# ETHERNET.net
KiCad netlist of a schematic drawn in Altium Designer
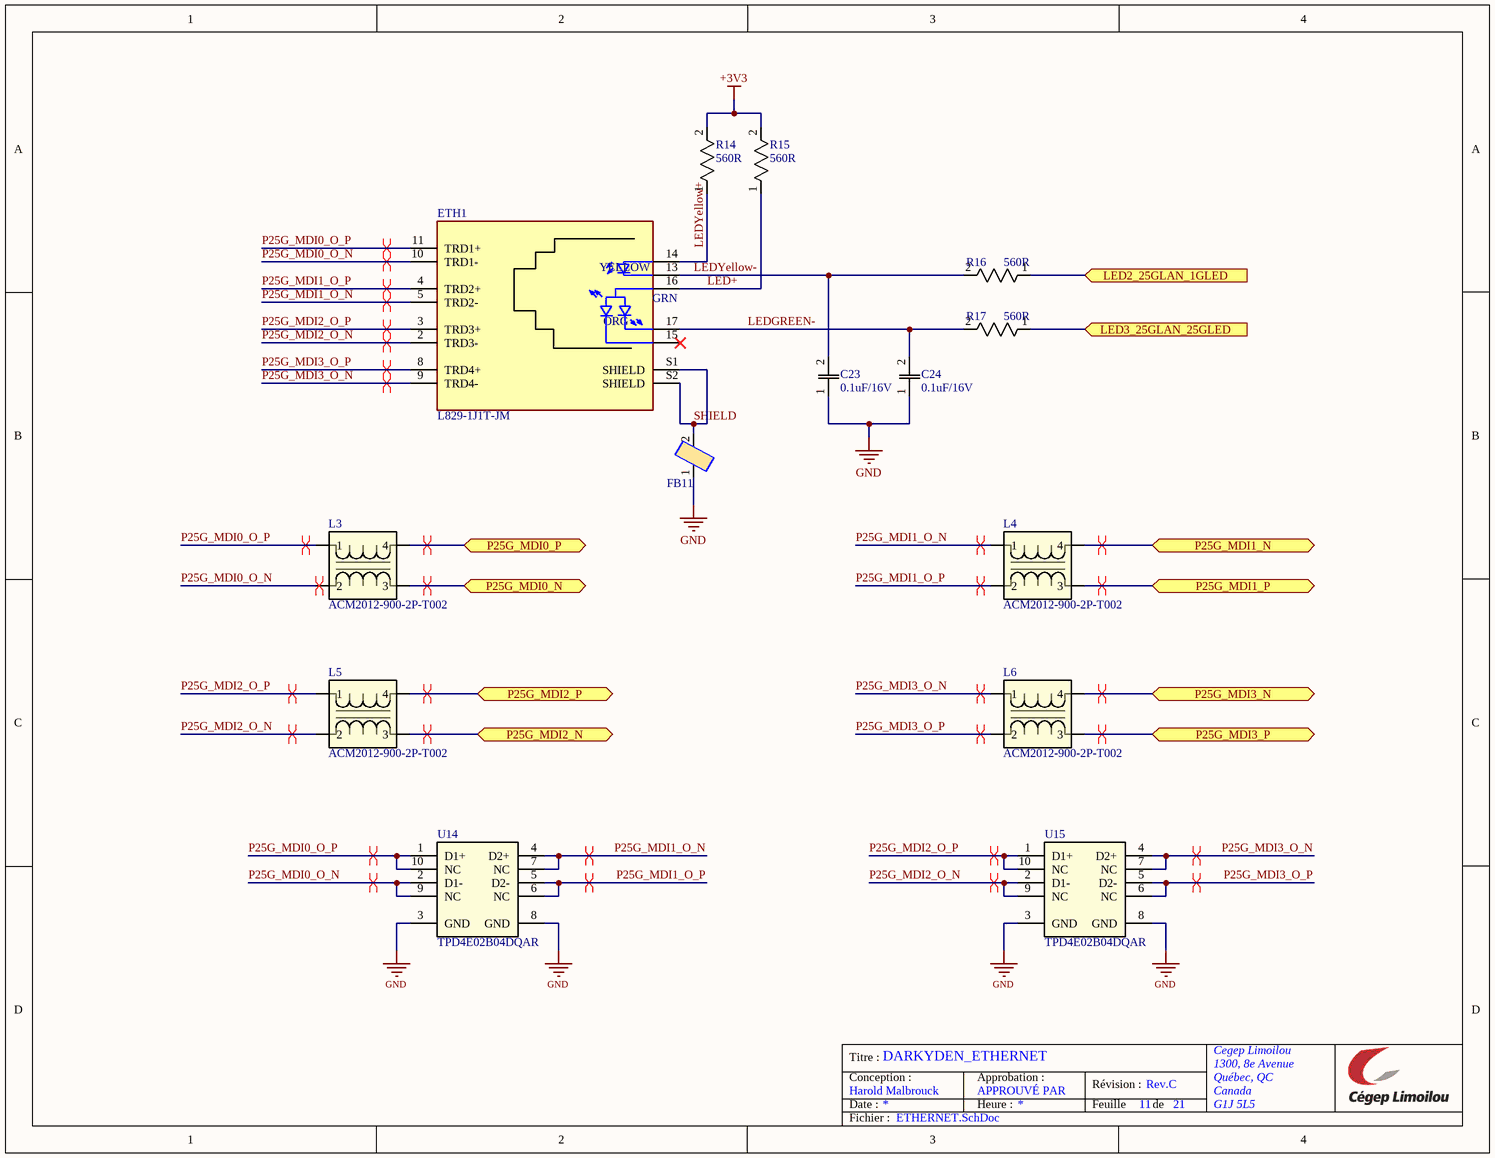
[diagram p0: ETHERNET.SchDoc]

(export (version "E")
  (design (tool "Eeschema 10.0.6"))
  (components
    (comp (ref "C23")
      (value "0.1uF/16V")
      (footprint "C0805")
      (description "0.1uF/16V ±10% X7R 0805 (2012METRIC) Ceramic Capacitor SMD Auto X7R")
      (fields
        (field (name "MANUFACTURER") "KEMET")
        (field (name "MANUFACTURER PART NUMBER") "C0805C104K5RACTU")
      )
      (libsource (lib "DARKYDEN") (part "C0805C104K4RACAUTO"))
    )
    (comp (ref "C24")
      (value "0.1uF/16V")
      (footprint "C0805")
      (description "0.1uF/16V ±10% X7R 0805 (2012METRIC) Ceramic Capacitor SMD Auto X7R")
      (fields
        (field (name "MANUFACTURER") "KEMET")
        (field (name "MANUFACTURER PART NUMBER") "C0805C104K5RACTU")
      )
      (libsource (lib "DARKYDEN") (part "C0805C104K4RACAUTO"))
    )
    (comp (ref "ETH1")
      (value "L829-1J1T-JM")
      (footprint "RJ-45")
      (description "Modular Connectors / Ethernet Connectors 1x1 2.5GBT MagJack")
      (fields
        (field (name "DIGI-KEY_PART_NUMBER") "507-2068-ND")
        (field (name "MF") "Bel Magnetic Solutions")
      )
      (libsource (lib "L829-1J1T-JM") (part "L829-1J1T-JM"))
    )
    (comp (ref "FB11")
      (value "220R / 100MHz")
      (footprint "SamacSys:BLM18SP221SN1B")
      (description "Ferrite Beads Multi-Layer 220Ohm 25% 100MHz 2A 50mOhm DCR 0603 Paper T/R")
      (fields
        (field (name "MOUSER PART NUMBER") "81-BLM18EG221SN1D")
        (field (name "ARROW PART NUMBER") "BLM18EG221SN1D")
      )
      (libsource (lib "SamacSys") (part "BLM18EG221SN1D"))
    )
    (comp (ref "L3")
      (value "ACM2012-900-2P-T002")
      (footprint "SamacSys:ACM20129002PT002")
      (description "Ferrite Beads Wirewound Common Mode Filter 90Ohm 100MHz 400mA 0805 T/R")
      (fields (field (name "MOUSER PART NUMBER") "810-ACM20129002PT002") (field (name "MANUFACTURER") "TDK"))
      (libsource (lib "SamacSys") (part "ACM2012-900-2P-T002"))
    )
    (comp (ref "L4")
      (value "ACM2012-900-2P-T002")
      (footprint "SamacSys:ACM20129002PT002")
      (description "Ferrite Beads Wirewound Common Mode Filter 90Ohm 100MHz 400mA 0805 T/R")
      (fields (field (name "MOUSER PART NUMBER") "810-ACM20129002PT002") (field (name "MANUFACTURER") "TDK"))
      (libsource (lib "SamacSys") (part "ACM2012-900-2P-T002"))
    )
    (comp (ref "L5")
      (value "ACM2012-900-2P-T002")
      (footprint "SamacSys:ACM20129002PT002")
      (description "Ferrite Beads Wirewound Common Mode Filter 90Ohm 100MHz 400mA 0805 T/R")
      (fields (field (name "MOUSER PART NUMBER") "810-ACM20129002PT002") (field (name "MANUFACTURER") "TDK"))
      (libsource (lib "SamacSys") (part "ACM2012-900-2P-T002"))
    )
    (comp (ref "L6")
      (value "ACM2012-900-2P-T002")
      (footprint "SamacSys:ACM20129002PT002")
      (description "Ferrite Beads Wirewound Common Mode Filter 90Ohm 100MHz 400mA 0805 T/R")
      (fields (field (name "MOUSER PART NUMBER") "810-ACM20129002PT002") (field (name "MANUFACTURER") "TDK"))
      (libsource (lib "SamacSys") (part "ACM2012-900-2P-T002"))
    )
    (comp (ref "R14")
      (value "560R")
      (footprint "RESC1608X55N")
      (description "560 Ohm, ï¿½ 1%, 100 mW, 0603 [1608 Metric], Thick Film, Precision")
      (fields
        (field (name "MANUFACTURER") "Panasonic")
        (field (name "MANUFACTURER PART NUMBER") "ERJ-3EKF5600V")
      )
      (libsource (lib "DARKYDEN") (part "ERJ-3EKF5600V"))
    )
    (comp (ref "R15")
      (value "560R")
      (footprint "RESC1608X55N")
      (description "560 Ohm, ï¿½ 1%, 100 mW, 0603 [1608 Metric], Thick Film, Precision")
      (fields
        (field (name "MANUFACTURER") "Panasonic")
        (field (name "MANUFACTURER PART NUMBER") "ERJ-3EKF5600V")
      )
      (libsource (lib "DARKYDEN") (part "ERJ-3EKF5600V"))
    )
    (comp (ref "R16")
      (value "560R")
      (footprint "RESC1608X55N")
      (description "560 Ohm, ï¿½ 1%, 100 mW, 0603 [1608 Metric], Thick Film, Precision")
      (fields
        (field (name "MANUFACTURER") "Panasonic")
        (field (name "MANUFACTURER PART NUMBER") "ERJ-3EKF5600V")
      )
      (libsource (lib "DARKYDEN") (part "ERJ-3EKF5600V"))
    )
    (comp (ref "R17")
      (value "560R")
      (footprint "RESC1608X55N")
      (description "560 Ohm, ï¿½ 1%, 100 mW, 0603 [1608 Metric], Thick Film, Precision")
      (fields
        (field (name "MANUFACTURER") "Panasonic")
        (field (name "MANUFACTURER PART NUMBER") "ERJ-3EKF5600V")
      )
      (libsource (lib "DARKYDEN") (part "ERJ-3EKF5600V"))
    )
    (comp (ref "U14")
      (value "TPD4E02B04DQAR")
      (footprint "DQA0010A")
      (description "TVS DIODE 3.6V 8.8V 10USON / 4-Channel ESD Protection Diode for USB Type-C and HDMI 2.0")
      (fields (field (name "MANUFACTURER") "Texas Instruments"))
      (libsource (lib "TPD4E02B04DQAR") (part "TPD4E02B04DQAR"))
    )
    (comp (ref "U15")
      (value "TPD4E02B04DQAR")
      (footprint "DQA0010A")
      (description "TVS DIODE 3.6V 8.8V 10USON / 4-Channel ESD Protection Diode for USB Type-C and HDMI 2.0")
      (fields (field (name "MANUFACTURER") "Texas Instruments"))
      (libsource (lib "TPD4E02B04DQAR") (part "TPD4E02B04DQAR"))
    )
  )
  (nets
    (net (code "1") (name "+3V3") (class "Default")
      (node (ref "R14") (pin "2") (pinfunction "2_2") (pintype "passive"))
      (node (ref "R15") (pin "2") (pinfunction "2_2") (pintype "passive"))
    )
    (net (code "2") (name "/LED+") (class "Default")
      (node (ref "ETH1") (pin "16") (pinfunction "CA_16") (pintype "passive"))
      (node (ref "R15") (pin "1") (pinfunction "1_1") (pintype "passive"))
    )
    (net (code "3") (name "/LED2_25GLAN_1GLED") (class "Default")
      (node (ref "R16") (pin "1") (pinfunction "1_1") (pintype "passive"))
    )
    (net (code "4") (name "/LED3_25GLAN_25GLED") (class "Default")
      (node (ref "R17") (pin "1") (pinfunction "1_1") (pintype "passive"))
    )
    (net (code "5") (name "/LEDGREEN-") (class "Default")
      (node (ref "C24") (pin "2") (pinfunction "2_2") (pintype "passive"))
      (node (ref "ETH1") (pin "17") (pinfunction "GK_1_17") (pintype "passive"))
      (node (ref "R17") (pin "2") (pinfunction "2_2") (pintype "passive"))
    )
    (net (code "6") (name "/LEDYellow+") (class "Default")
      (node (ref "ETH1") (pin "14") (pinfunction "YA_1_14") (pintype "passive"))
      (node (ref "R14") (pin "1") (pinfunction "1_1") (pintype "passive"))
    )
    (net (code "7") (name "/LEDYellow-") (class "Default")
      (node (ref "C23") (pin "2") (pinfunction "2_2") (pintype "passive"))
      (node (ref "ETH1") (pin "13") (pinfunction "YK_1_13") (pintype "passive"))
      (node (ref "R16") (pin "2") (pinfunction "2_2") (pintype "passive"))
    )
    (net (code "8") (name "/P25G_MDI0_N") (class "Default")
      (node (ref "L3") (pin "3") (pinfunction "3_3") (pintype "passive"))
    )
    (net (code "9") (name "/P25G_MDI0_O_N") (class "Default")
      (node (ref "ETH1") (pin "10") (pinfunction "TRD1-_10") (pintype "passive"))
      (node (ref "L3") (pin "2") (pinfunction "2_2") (pintype "passive"))
      (node (ref "U14") (pin "2") (pinfunction "D1-_2") (pintype "passive"))
      (node (ref "U14") (pin "9") (pinfunction "NC_9") (pintype "passive"))
    )
    (net (code "10") (name "/P25G_MDI0_O_P") (class "Default")
      (node (ref "ETH1") (pin "11") (pinfunction "TRD1+_11") (pintype "passive"))
      (node (ref "L3") (pin "1") (pinfunction "1_1") (pintype "passive"))
      (node (ref "U14") (pin "1") (pinfunction "D1+_1") (pintype "passive"))
      (node (ref "U14") (pin "10") (pinfunction "NC_10") (pintype "passive"))
    )
    (net (code "11") (name "/P25G_MDI0_P") (class "Default")
      (node (ref "L3") (pin "4") (pinfunction "4_4") (pintype "passive"))
    )
    (net (code "12") (name "/P25G_MDI1_N") (class "Default")
      (node (ref "L4") (pin "4") (pinfunction "4_4") (pintype "passive"))
    )
    (net (code "13") (name "/P25G_MDI1_O_N") (class "Default")
      (node (ref "ETH1") (pin "5") (pinfunction "TRD2-_5") (pintype "passive"))
      (node (ref "L4") (pin "1") (pinfunction "1_1") (pintype "passive"))
      (node (ref "U14") (pin "4") (pinfunction "D2+_4") (pintype "passive"))
      (node (ref "U14") (pin "7") (pinfunction "NC_7") (pintype "passive"))
    )
    (net (code "14") (name "/P25G_MDI1_O_P") (class "Default")
      (node (ref "ETH1") (pin "4") (pinfunction "TRD2+_4") (pintype "passive"))
      (node (ref "L4") (pin "2") (pinfunction "2_2") (pintype "passive"))
      (node (ref "U14") (pin "5") (pinfunction "D2-_5") (pintype "passive"))
      (node (ref "U14") (pin "6") (pinfunction "NC_6") (pintype "passive"))
    )
    (net (code "15") (name "/P25G_MDI1_P") (class "Default")
      (node (ref "L4") (pin "3") (pinfunction "3_3") (pintype "passive"))
    )
    (net (code "16") (name "/P25G_MDI2_N") (class "Default")
      (node (ref "L5") (pin "3") (pinfunction "3_3") (pintype "passive"))
    )
    (net (code "17") (name "/P25G_MDI2_O_N") (class "Default")
      (node (ref "ETH1") (pin "2") (pinfunction "TRD3-_2") (pintype "passive"))
      (node (ref "L5") (pin "2") (pinfunction "2_2") (pintype "passive"))
      (node (ref "U15") (pin "2") (pinfunction "D1-_2") (pintype "passive"))
      (node (ref "U15") (pin "9") (pinfunction "NC_9") (pintype "passive"))
    )
    (net (code "18") (name "/P25G_MDI2_O_P") (class "Default")
      (node (ref "ETH1") (pin "3") (pinfunction "TRD3+_3") (pintype "passive"))
      (node (ref "L5") (pin "1") (pinfunction "1_1") (pintype "passive"))
      (node (ref "U15") (pin "1") (pinfunction "D1+_1") (pintype "passive"))
      (node (ref "U15") (pin "10") (pinfunction "NC_10") (pintype "passive"))
    )
    (net (code "19") (name "/P25G_MDI2_P") (class "Default")
      (node (ref "L5") (pin "4") (pinfunction "4_4") (pintype "passive"))
    )
    (net (code "20") (name "/P25G_MDI3_N") (class "Default")
      (node (ref "L6") (pin "4") (pinfunction "4_4") (pintype "passive"))
    )
    (net (code "21") (name "/P25G_MDI3_O_N") (class "Default")
      (node (ref "ETH1") (pin "9") (pinfunction "TRD4-_9") (pintype "passive"))
      (node (ref "L6") (pin "1") (pinfunction "1_1") (pintype "passive"))
      (node (ref "U15") (pin "4") (pinfunction "D2+_4") (pintype "passive"))
      (node (ref "U15") (pin "7") (pinfunction "NC_7") (pintype "passive"))
    )
    (net (code "22") (name "/P25G_MDI3_O_P") (class "Default")
      (node (ref "ETH1") (pin "8") (pinfunction "TRD4+_8") (pintype "passive"))
      (node (ref "L6") (pin "2") (pinfunction "2_2") (pintype "passive"))
      (node (ref "U15") (pin "5") (pinfunction "D2-_5") (pintype "passive"))
      (node (ref "U15") (pin "6") (pinfunction "NC_6") (pintype "passive"))
    )
    (net (code "23") (name "/P25G_MDI3_P") (class "Default")
      (node (ref "L6") (pin "3") (pinfunction "3_3") (pintype "passive"))
    )
    (net (code "24") (name "/SHIELD") (class "Default")
      (node (ref "ETH1") (pin "S1") (pinfunction "SHIELD_S1") (pintype "passive"))
      (node (ref "ETH1") (pin "S2") (pinfunction "SHIELD_S2") (pintype "passive"))
      (node (ref "FB11") (pin "2") (pinfunction "2_2") (pintype "passive"))
    )
    (net (code "25") (name "GND") (class "Default")
      (node (ref "C23") (pin "1") (pinfunction "1_1") (pintype "passive"))
      (node (ref "C24") (pin "1") (pinfunction "1_1") (pintype "passive"))
      (node (ref "FB11") (pin "1") (pinfunction "1_1") (pintype "passive"))
      (node (ref "U14") (pin "3") (pinfunction "GND_3") (pintype "passive"))
      (node (ref "U14") (pin "8") (pinfunction "GND_8") (pintype "passive"))
      (node (ref "U15") (pin "3") (pinfunction "GND_3") (pintype "passive"))
      (node (ref "U15") (pin "8") (pinfunction "GND_8") (pintype "passive"))
    )
    (net (code "26") (name "unconnected-(ETH1-OK_1-Pad15)") (class "Default")
      (node (ref "ETH1") (pin "15") (pinfunction "OK_1_15") (pintype "passive+no_connect"))
    )
    (net (code "27") (name "unconnected-(ETH1-TRCT1-Pad12)") (class "Default")
      (node (ref "ETH1") (pin "12") (pinfunction "TRCT1_12") (pintype "passive"))
    )
    (net (code "28") (name "unconnected-(ETH1-TRCT2-Pad6)") (class "Default")
      (node (ref "ETH1") (pin "6") (pinfunction "TRCT2_6") (pintype "passive"))
    )
    (net (code "29") (name "unconnected-(ETH1-TRCT3-Pad1)") (class "Default")
      (node (ref "ETH1") (pin "1") (pinfunction "TRCT3_1") (pintype "passive"))
    )
    (net (code "30") (name "unconnected-(ETH1-TRCT4-Pad7)") (class "Default")
      (node (ref "ETH1") (pin "7") (pinfunction "TRCT4_7") (pintype "passive"))
    )
  )
)
